# OSSI-1_OBC_2.net
KiCad netlist of a schematic drawn in Altium Designer
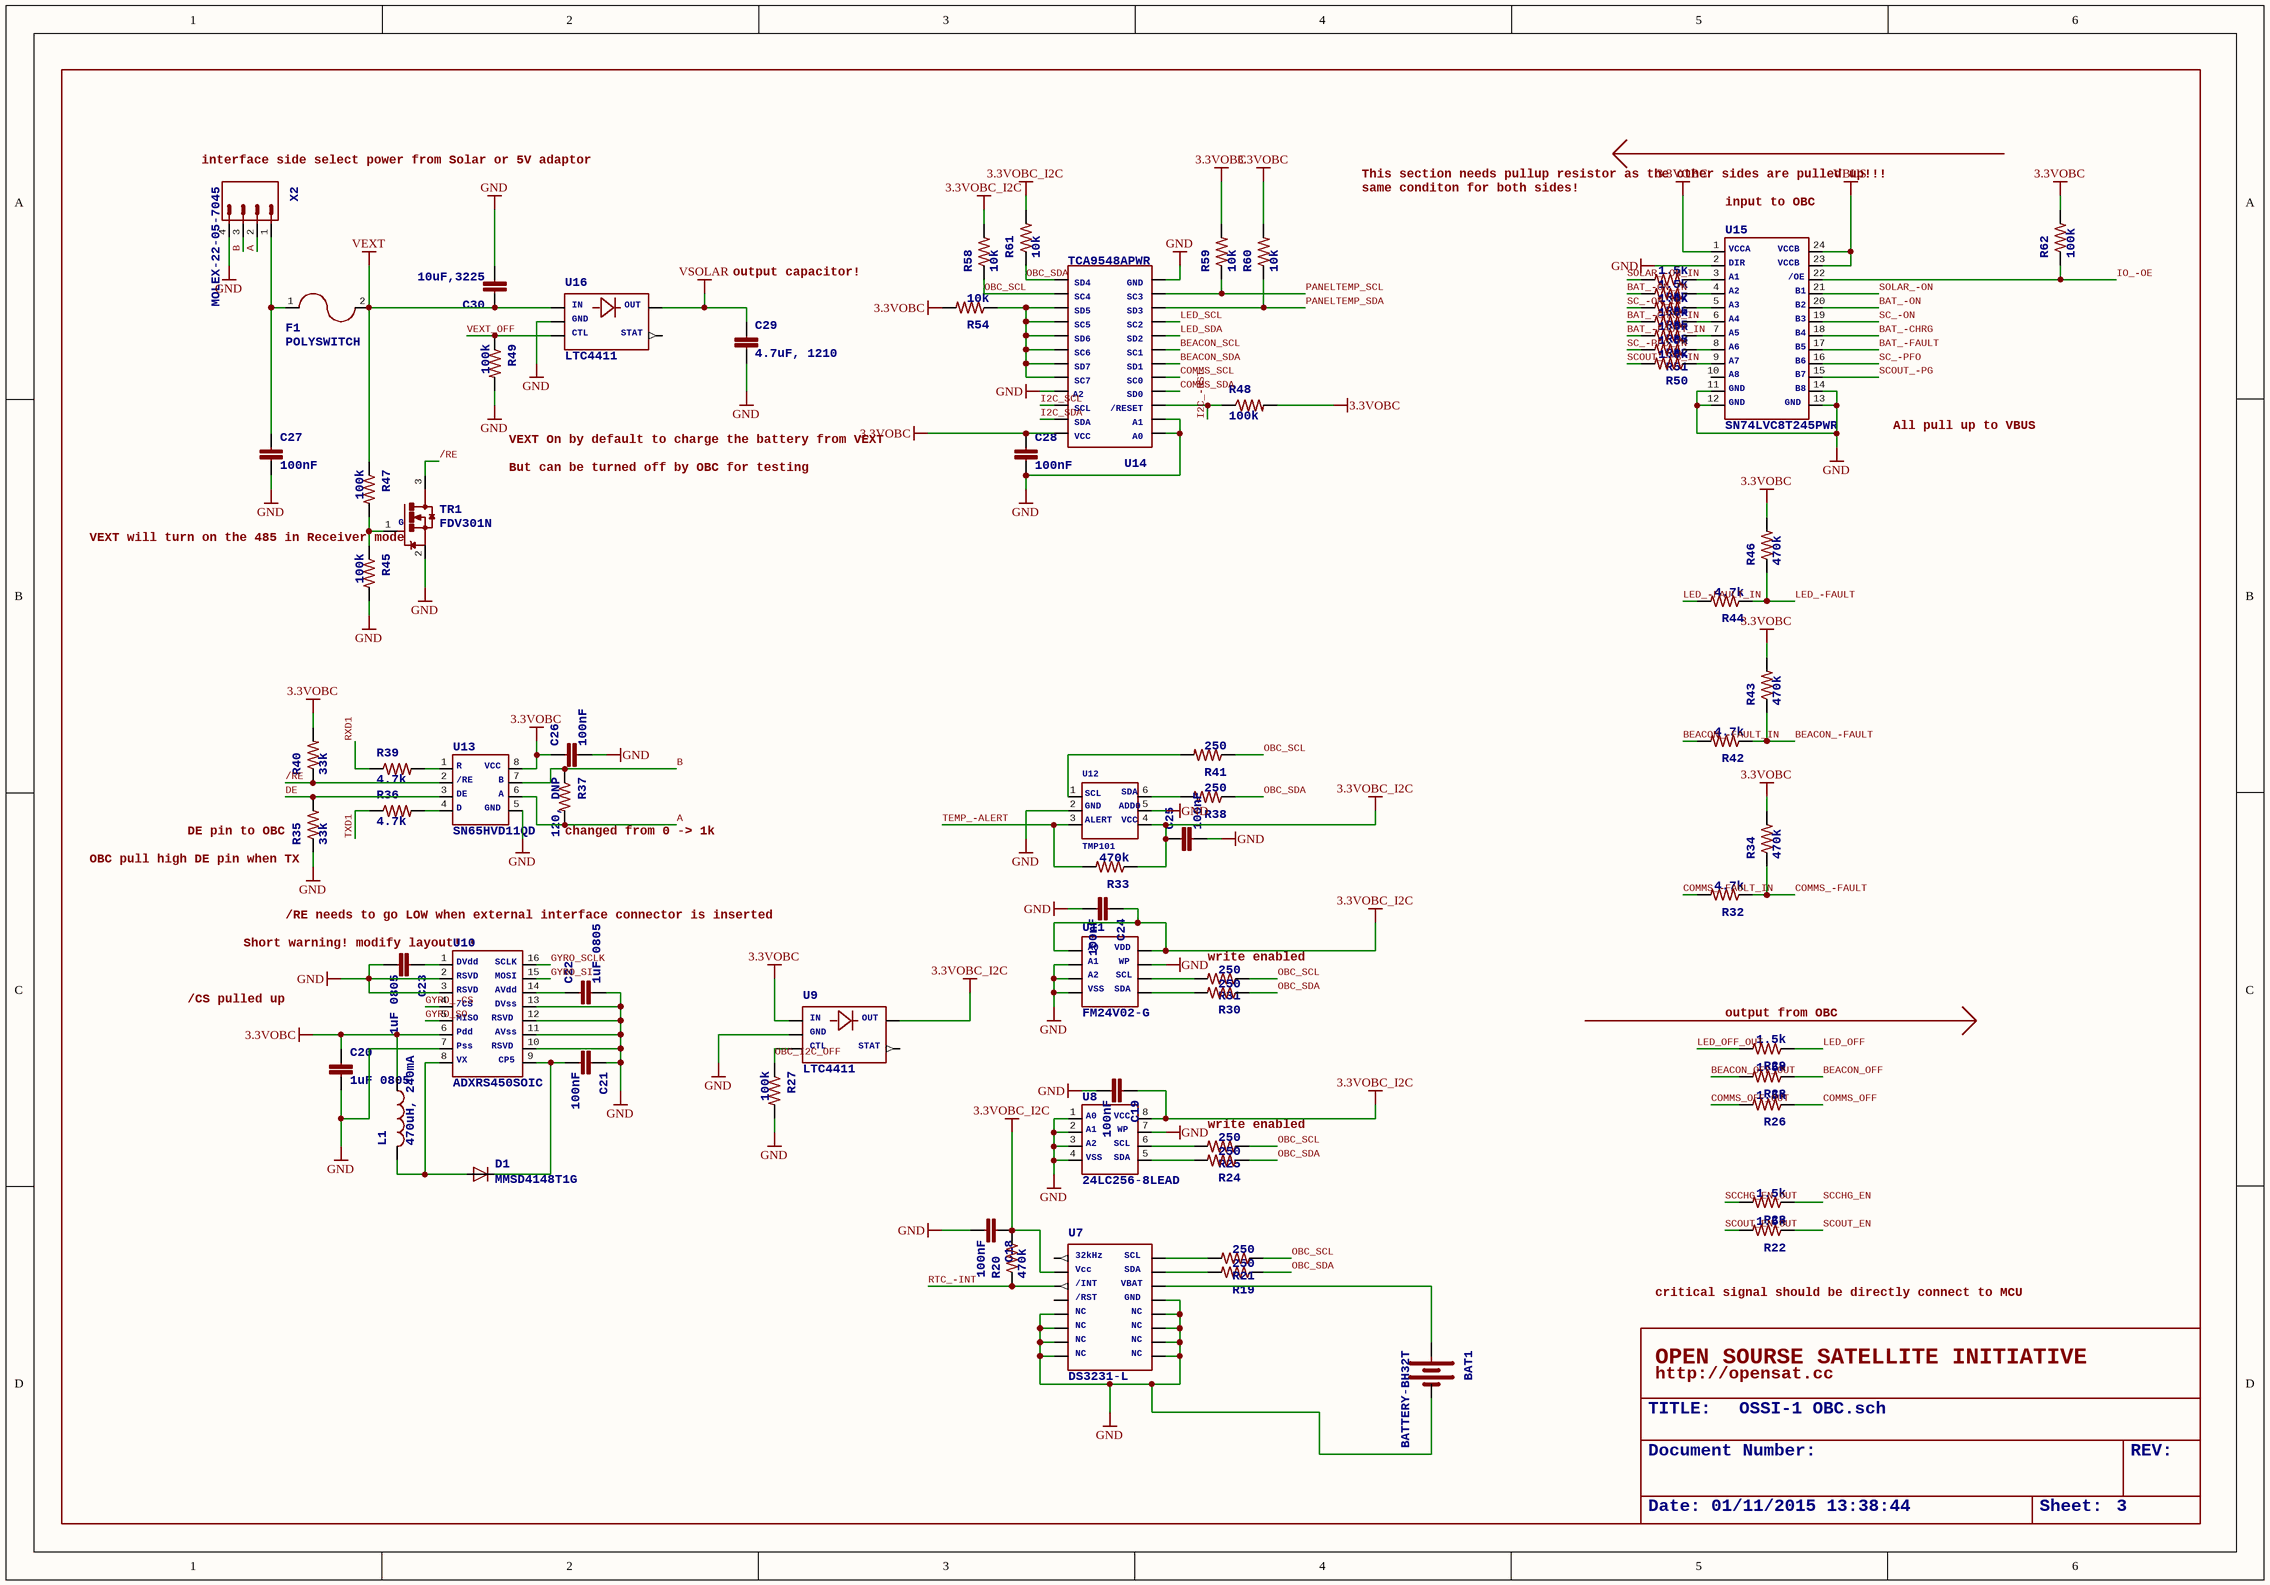
[diagram p0: OSSI-1 OBC_2.SchDoc]

(export (version "E")
  (design (tool "Eeschema 10.0.6"))
  (components
    (comp (ref "BAT1")
      (value "BATTERY-BH32T")
      (footprint "BH32T-C-G")
      (fields (field (name ">NAME") "BAT1") (field (name ">VALUE") "BATTERY-BH32T"))
      (libsource (lib "OSSI") (part "BATTERY-BH32T"))
    )
    (comp (ref "C18")
      (value "100nF")
      (footprint "C0603(1608)")
      (fields (field (name ">NAME") "C18") (field (name ">VALUE") "100nF"))
      (libsource (lib "OSSI") (part "C0603(1608)"))
    )
    (comp (ref "C19")
      (value "100nF")
      (footprint "C0603(1608)")
      (fields (field (name ">NAME") "C19") (field (name ">VALUE") "100nF"))
      (libsource (lib "OSSI") (part "C0603(1608)"))
    )
    (comp (ref "C20")
      (value "1uF 0805")
      (footprint "C0805(2012)")
      (fields (field (name ">NAME") "C20") (field (name ">VALUE") "1uF 0805"))
      (libsource (lib "") (part "C0805(2012)_2"))
    )
    (comp (ref "C21")
      (value "100nF")
      (footprint "C0603(1608)")
      (fields (field (name ">NAME") "C21") (field (name ">VALUE") "100nF"))
      (libsource (lib "OSSI") (part "C0603(1608)"))
    )
    (comp (ref "C22")
      (value "1uF 0805")
      (footprint "C0805(2012)")
      (fields (field (name ">NAME") "C22") (field (name ">VALUE") "1uF 0805"))
      (libsource (lib "OSSI") (part "C0805(2012)"))
    )
    (comp (ref "C23")
      (value "1uF 0805")
      (footprint "C0805(2012)")
      (fields (field (name ">NAME") "C23") (field (name ">VALUE") "1uF 0805"))
      (libsource (lib "") (part "C0805(2012)_1"))
    )
    (comp (ref "C24")
      (value "100nF")
      (footprint "C0603(1608)")
      (fields (field (name ">NAME") "C24") (field (name ">VALUE") "100nF"))
      (libsource (lib "OSSI") (part "C0603(1608)"))
    )
    (comp (ref "C25")
      (value "100nF")
      (footprint "C0603(1608)")
      (fields (field (name ">NAME") "C25") (field (name ">VALUE") "100nF"))
      (libsource (lib "") (part "C0603(1608)_1"))
    )
    (comp (ref "C26")
      (value "100nF")
      (footprint "C0603(1608)")
      (fields (field (name ">NAME") "C26") (field (name ">VALUE") "100nF"))
      (libsource (lib "") (part "C0603(1608)_1"))
    )
    (comp (ref "C27")
      (value "100nF")
      (footprint "C0603(1608)")
      (fields (field (name ">NAME") "C27") (field (name ">VALUE") "100nF"))
      (libsource (lib "") (part "C0603(1608)_2"))
    )
    (comp (ref "C28")
      (value "100nF")
      (footprint "C0603(1608)")
      (fields (field (name ">NAME") "C28") (field (name ">VALUE") "100nF"))
      (libsource (lib "") (part "C0603(1608)_2"))
    )
    (comp (ref "C29")
      (value "4.7uF, 1210")
      (footprint "C1206-GCM31")
      (fields (field (name ">NAME") "C29") (field (name ">VALUE") "4.7uF, 1210"))
      (libsource (lib "OSSI") (part "C1206(3216)-GCM31"))
    )
    (comp (ref "C30")
      (value "10uF,3225")
      (footprint "C1210-GCM32")
      (fields (field (name ">NAME") "C30") (field (name ">VALUE") "10uF,3225"))
      (libsource (lib "OSSI") (part "C1210(3225)-GCM32"))
    )
    (comp (ref "D1")
      (value "MMSD4148T1G")
      (footprint "SOD-123")
      (fields (field (name ">NAME") "D1") (field (name ">VALUE") "MMSD4148T1G"))
      (libsource (lib "OSSI") (part "MMSD4148T1G"))
    )
    (comp (ref "F1")
      (value "POLYSWITCH")
      (footprint "NANOSMDC150FCT")
      (description "Resettable Polyswitch")
      (fields (field (name ">NAME") "F1") (field (name ">VALUE") "POLYSWITCH"))
      (libsource (lib "OSSI") (part "POLYSWITCH"))
    )
    (comp (ref "L1")
      (value "470uH, 240mA")
      (footprint "L(2220)")
      (fields (field (name ">NAME") "L1") (field (name ">VALUE") "470uH, 240mA"))
      (libsource (lib "OSSI") (part "LQH55"))
    )
    (comp (ref "R19")
      (value "250")
      (footprint "R0603(1608)")
      (fields (field (name ">NAME") "R19") (field (name ">VALUE") "250"))
      (libsource (lib "OSSI") (part "R0603(1608)"))
    )
    (comp (ref "R20")
      (value "470k")
      (footprint "R0603(1608)")
      (fields (field (name ">NAME") "R20") (field (name ">VALUE") "470k"))
      (libsource (lib "OSSI") (part "R0603(1608)"))
    )
    (comp (ref "R21")
      (value "250")
      (footprint "R0603(1608)")
      (fields (field (name ">NAME") "R21") (field (name ">VALUE") "250"))
      (libsource (lib "OSSI") (part "R0603(1608)"))
    )
    (comp (ref "R22")
      (value "1.5k")
      (footprint "R0603(1608)")
      (fields (field (name ">NAME") "R22") (field (name ">VALUE") "1.5k"))
      (libsource (lib "OSSI") (part "R0603(1608)"))
    )
    (comp (ref "R23")
      (value "1.5k")
      (footprint "R0603(1608)")
      (fields (field (name ">NAME") "R23") (field (name ">VALUE") "1.5k"))
      (libsource (lib "OSSI") (part "R0603(1608)"))
    )
    (comp (ref "R24")
      (value "250")
      (footprint "R0603(1608)")
      (fields (field (name ">NAME") "R24") (field (name ">VALUE") "250"))
      (libsource (lib "OSSI") (part "R0603(1608)"))
    )
    (comp (ref "R25")
      (value "250")
      (footprint "R0603(1608)")
      (fields (field (name ">NAME") "R25") (field (name ">VALUE") "250"))
      (libsource (lib "OSSI") (part "R0603(1608)"))
    )
    (comp (ref "R26")
      (value "1.5k")
      (footprint "R0603(1608)")
      (fields (field (name ">NAME") "R26") (field (name ">VALUE") "1.5k"))
      (libsource (lib "OSSI") (part "R0603(1608)"))
    )
    (comp (ref "R27")
      (value "100k")
      (footprint "R0603(1608)")
      (fields (field (name ">NAME") "R27") (field (name ">VALUE") "100k"))
      (libsource (lib "OSSI") (part "R0603(1608)"))
    )
    (comp (ref "R28")
      (value "1.5k")
      (footprint "R0603(1608)")
      (fields (field (name ">NAME") "R28") (field (name ">VALUE") "1.5k"))
      (libsource (lib "OSSI") (part "R0603(1608)"))
    )
    (comp (ref "R29")
      (value "1.5k")
      (footprint "R0603(1608)")
      (fields (field (name ">NAME") "R29") (field (name ">VALUE") "1.5k"))
      (libsource (lib "OSSI") (part "R0603(1608)"))
    )
    (comp (ref "R30")
      (value "250")
      (footprint "R0603(1608)")
      (fields (field (name ">NAME") "R30") (field (name ">VALUE") "250"))
      (libsource (lib "OSSI") (part "R0603(1608)"))
    )
    (comp (ref "R31")
      (value "250")
      (footprint "R0603(1608)")
      (fields (field (name ">NAME") "R31") (field (name ">VALUE") "250"))
      (libsource (lib "OSSI") (part "R0603(1608)"))
    )
    (comp (ref "R32")
      (value "4.7k")
      (footprint "R0603(1608)")
      (fields (field (name ">NAME") "R32") (field (name ">VALUE") "4.7k"))
      (libsource (lib "OSSI") (part "R0603(1608)"))
    )
    (comp (ref "R33")
      (value "470k")
      (footprint "R0603(1608)")
      (fields (field (name ">NAME") "R33") (field (name ">VALUE") "470k"))
      (libsource (lib "OSSI") (part "R0603(1608)"))
    )
    (comp (ref "R34")
      (value "470k")
      (footprint "R0603(1608)")
      (fields (field (name ">NAME") "R34") (field (name ">VALUE") "470k"))
      (libsource (lib "OSSI") (part "R0603(1608)"))
    )
    (comp (ref "R35")
      (value "33k")
      (footprint "R0603(1608)")
      (fields (field (name ">NAME") "R35") (field (name ">VALUE") "33k"))
      (libsource (lib "OSSI") (part "R0603(1608)"))
    )
    (comp (ref "R36")
      (value "4.7k")
      (footprint "R0603(1608)")
      (fields (field (name ">NAME") "R36") (field (name ">VALUE") "4.7k"))
      (libsource (lib "OSSI") (part "R0603(1608)"))
    )
    (comp (ref "R37")
      (value "120, DNP")
      (footprint "R0603(1608)")
      (fields (field (name ">NAME") "R37") (field (name ">VALUE") "120, DNP"))
      (libsource (lib "OSSI") (part "R0603(1608)"))
    )
    (comp (ref "R38")
      (value "250")
      (footprint "R0603(1608)")
      (fields (field (name ">NAME") "R38") (field (name ">VALUE") "250"))
      (libsource (lib "OSSI") (part "R0603(1608)"))
    )
    (comp (ref "R39")
      (value "4.7k")
      (footprint "R0603(1608)")
      (fields (field (name ">NAME") "R39") (field (name ">VALUE") "4.7k"))
      (libsource (lib "OSSI") (part "R0603(1608)"))
    )
    (comp (ref "R40")
      (value "33k")
      (footprint "R0603(1608)")
      (fields (field (name ">NAME") "R40") (field (name ">VALUE") "33k"))
      (libsource (lib "OSSI") (part "R0603(1608)"))
    )
    (comp (ref "R41")
      (value "250")
      (footprint "R0603(1608)")
      (fields (field (name ">NAME") "R41") (field (name ">VALUE") "250"))
      (libsource (lib "OSSI") (part "R0603(1608)"))
    )
    (comp (ref "R42")
      (value "4.7k")
      (footprint "R0603(1608)")
      (fields (field (name ">NAME") "R42") (field (name ">VALUE") "4.7k"))
      (libsource (lib "OSSI") (part "R0603(1608)"))
    )
    (comp (ref "R43")
      (value "470k")
      (footprint "R0603(1608)")
      (fields (field (name ">NAME") "R43") (field (name ">VALUE") "470k"))
      (libsource (lib "OSSI") (part "R0603(1608)"))
    )
    (comp (ref "R44")
      (value "4.7k")
      (footprint "R0603(1608)")
      (fields (field (name ">NAME") "R44") (field (name ">VALUE") "4.7k"))
      (libsource (lib "OSSI") (part "R0603(1608)"))
    )
    (comp (ref "R45")
      (value "100k")
      (footprint "R0603(1608)")
      (fields (field (name ">NAME") "R45") (field (name ">VALUE") "100k"))
      (libsource (lib "OSSI") (part "R0603(1608)"))
    )
    (comp (ref "R46")
      (value "470k")
      (footprint "R0603(1608)")
      (fields (field (name ">NAME") "R46") (field (name ">VALUE") "470k"))
      (libsource (lib "OSSI") (part "R0603(1608)"))
    )
    (comp (ref "R47")
      (value "100k")
      (footprint "R0603(1608)")
      (fields (field (name ">NAME") "R47") (field (name ">VALUE") "100k"))
      (libsource (lib "OSSI") (part "R0603(1608)"))
    )
    (comp (ref "R48")
      (value "100k")
      (footprint "R0603(1608)")
      (fields (field (name ">NAME") "R48") (field (name ">VALUE") "100k"))
      (libsource (lib "OSSI") (part "R0603(1608)"))
    )
    (comp (ref "R49")
      (value "100k")
      (footprint "R0603(1608)")
      (fields (field (name ">NAME") "R49") (field (name ">VALUE") "100k"))
      (libsource (lib "OSSI") (part "R0603(1608)"))
    )
    (comp (ref "R50")
      (value "1.5k")
      (footprint "R0603(1608)")
      (fields (field (name ">NAME") "R50") (field (name ">VALUE") "1.5k"))
      (libsource (lib "OSSI") (part "R0603(1608)"))
    )
    (comp (ref "R51")
      (value "1.5k")
      (footprint "R0603(1608)")
      (fields (field (name ">NAME") "R51") (field (name ">VALUE") "1.5k"))
      (libsource (lib "OSSI") (part "R0603(1608)"))
    )
    (comp (ref "R52")
      (value "1.5k")
      (footprint "R0603(1608)")
      (fields (field (name ">NAME") "R52") (field (name ">VALUE") "1.5k"))
      (libsource (lib "OSSI") (part "R0603(1608)"))
    )
    (comp (ref "R53")
      (value "1.5k")
      (footprint "R0603(1608)")
      (fields (field (name ">NAME") "R53") (field (name ">VALUE") "1.5k"))
      (libsource (lib "OSSI") (part "R0603(1608)"))
    )
    (comp (ref "R54")
      (value "10k")
      (footprint "R0603(1608)")
      (fields (field (name ">NAME") "R54") (field (name ">VALUE") "10k"))
      (libsource (lib "OSSI") (part "R0603(1608)"))
    )
    (comp (ref "R55")
      (value "1.5k")
      (footprint "R0603(1608)")
      (fields (field (name ">NAME") "R55") (field (name ">VALUE") "1.5k"))
      (libsource (lib "OSSI") (part "R0603(1608)"))
    )
    (comp (ref "R56")
      (value "1.5k")
      (footprint "R0603(1608)")
      (fields (field (name ">NAME") "R56") (field (name ">VALUE") "1.5k"))
      (libsource (lib "OSSI") (part "R0603(1608)"))
    )
    (comp (ref "R57")
      (value "1.5k")
      (footprint "R0603(1608)")
      (fields (field (name ">NAME") "R57") (field (name ">VALUE") "1.5k"))
      (libsource (lib "OSSI") (part "R0603(1608)"))
    )
    (comp (ref "R58")
      (value "10k")
      (footprint "R0603(1608)")
      (fields (field (name ">NAME") "R58") (field (name ">VALUE") "10k"))
      (libsource (lib "OSSI") (part "R0603(1608)"))
    )
    (comp (ref "R59")
      (value "10k")
      (footprint "R0603(1608)")
      (fields (field (name ">NAME") "R59") (field (name ">VALUE") "10k"))
      (libsource (lib "OSSI") (part "R0603(1608)"))
    )
    (comp (ref "R60")
      (value "10k")
      (footprint "R0603(1608)")
      (fields (field (name ">NAME") "R60") (field (name ">VALUE") "10k"))
      (libsource (lib "OSSI") (part "R0603(1608)"))
    )
    (comp (ref "R61")
      (value "10k")
      (footprint "R0603(1608)")
      (fields (field (name ">NAME") "R61") (field (name ">VALUE") "10k"))
      (libsource (lib "OSSI") (part "R0603(1608)"))
    )
    (comp (ref "R62")
      (value "100k")
      (footprint "R0603(1608)")
      (fields (field (name ">NAME") "R62") (field (name ">VALUE") "100k"))
      (libsource (lib "OSSI") (part "R0603(1608)"))
    )
    (comp (ref "TR1")
      (value "FDV301N")
      (footprint "SOT23")
      (description "FDV301N Digital N channel - FET / Rdson = 5 Ohm / Vgs = 0.7~1.06V / Ids = 220mA")
      (fields (field (name "G") "G") (field (name ">NAME") "TR1") (field (name ">VALUE") "FDV301N"))
      (libsource (lib "OSSI") (part "FDV301N"))
    )
    (comp (ref "U7")
      (value "DS3231-L")
      (footprint "SO16L")
      (description "<b>DS3231</b>\n<br />\nExtremely Accureate I2C integrated RTC/TCXO/Crystal by MAXIM")
      (fields
        (field (name "32KHZ") "32kHz")
        (field (name "VCC") "Vcc")
        (field (name "/INT") "/INT")
        (field (name "/RST") "/RST")
        (field (name "NC") "NC")
        (field (name "NC_1") "NC")
        (field (name "NC_2") "NC")
        (field (name "NC_3") "NC")
        (field (name "NC_4") "NC")
        (field (name "NC_5") "NC")
        (field (name "NC_6") "NC")
        (field (name "NC_7") "NC")
        (field (name "GND") "GND")
        (field (name "VBAT") "VBAT")
        (field (name "SDA") "SDA")
        (field (name "SCL") "SCL")
        (field (name ">NAME") "U7")
        (field (name ">VALUE") "DS3231-L")
      )
      (libsource (lib "OSSI") (part "DS3231-L"))
    )
    (comp (ref "U8")
      (value "24LC256-8LEAD")
      (footprint "SO08-208")
      (description "24LC256<BR/>\n256K I2C™ CMOS Serial EEPROM")
      (fields
        (field (name ">NAME") "U8")
        (field (name ">VALUE") "24LC256-8LEAD")
        (field (name "A0") "A0")
        (field (name "A1") "A1")
        (field (name "A2") "A2")
        (field (name "VSS") "VSS")
        (field (name "VCC") "VCC")
        (field (name "WP") "WP")
        (field (name "SCL") "SCL")
        (field (name "SDA") "SDA")
      )
      (libsource (lib "OSSI") (part "24LC256-8LEAD"))
    )
    (comp (ref "U9")
      (value "LTC4411")
      (footprint "TSOT23-5")
      (fields
        (field (name "IN") "IN")
        (field (name "GND") "GND")
        (field (name "CTL") "CTL")
        (field (name "OUT") "OUT")
        (field (name "STAT") "STAT")
        (field (name ">NAME") "U9")
        (field (name ">VALUE") "LTC4411")
      )
      (libsource (lib "OSSI") (part "LTC4411"))
    )
    (comp (ref "U10")
      (value "ADXRS450SOIC")
      (footprint "SOIC-16CAV")
      (fields
        (field (name ">NAME") "U10")
        (field (name ">VALUE") "ADXRS450SOIC")
        (field (name "DVDD") "DVdd")
        (field (name "RSVD") "RSVD")
        (field (name "RSVD_1") "RSVD")
        (field (name "/CS") "/CS")
        (field (name "MISO") "MISO")
        (field (name "PDD") "Pdd")
        (field (name "PSS") "Pss")
        (field (name "VX") "VX")
        (field (name "CP5") "CP5")
        (field (name "RSVD_2") "RSVD")
        (field (name "AVSS") "AVss")
        (field (name "RSVD_3") "RSVD")
        (field (name "DVSS") "DVss")
        (field (name "AVDD") "AVdd")
        (field (name "MOSI") "MOSI")
        (field (name "SCLK") "SCLK")
      )
      (libsource (lib "OSSI") (part "ADXRS450SOIC"))
    )
    (comp (ref "U11")
      (value "FM24V02-G")
      (footprint "SO8")
      (description "<b>FM24V02</b>\n<br />\n256Kb Serial 3V F-RAM Memory by RAMTRON")
      (fields
        (field (name "A0") "A0")
        (field (name "A1") "A1")
        (field (name "A2") "A2")
        (field (name "VSS") "VSS")
        (field (name "SDA") "SDA")
        (field (name "SCL") "SCL")
        (field (name "WP") "WP")
        (field (name "VDD") "VDD")
        (field (name ">NAME") "U11")
        (field (name ">VALUE") "FM24V02-G")
      )
      (libsource (lib "OSSI") (part "FM24V02-G"))
    )
    (comp (ref "U12")
      (value "TMP101")
      (footprint "SOT23-6DBV")
      (description "TMP101 Digital Temerature Sensor with I2C Interface from Texas Instruments with Alert Function")
      (fields
        (field (name ">NAME") "U12")
        (field (name ">VALUE") "TMP101")
        (field (name "VCC") "VCC")
        (field (name "SCL") "SCL")
        (field (name "SDA") "SDA")
        (field (name "GND") "GND")
        (field (name "ADD0") "ADD0")
        (field (name "ALERT") "ALERT")
      )
      (libsource (lib "OSSI") (part "TMP101"))
    )
    (comp (ref "U13")
      (value "SN65HVD11QD")
      (footprint "SO8")
      (description "SN65HVD11 3.3V RS485 Transceiver <br />\nQD: -40~+125")
      (fields
        (field (name ">NAME") "U13")
        (field (name ">VALUE") "SN65HVD11QD")
        (field (name "R") "R")
        (field (name "/RE") "/RE")
        (field (name "DE") "DE")
        (field (name "D") "D")
        (field (name "VCC") "VCC")
        (field (name "B") "B")
        (field (name "A") "A")
        (field (name "GND") "GND")
      )
      (libsource (lib "OSSI") (part "SN65HVD11QD"))
    )
    (comp (ref "U14")
      (value "TCA9548APWR")
      (footprint "TSSOP-24-PW")
      (fields
        (field (name ">NAME") "U14")
        (field (name ">VALUE") "TCA9548APWR")
        (field (name "A0") "A0")
        (field (name "A1") "A1")
        (field (name "/RESET") "/RESET")
        (field (name "SD0") "SD0")
        (field (name "SC0") "SC0")
        (field (name "SD1") "SD1")
        (field (name "SC1") "SC1")
        (field (name "SD2") "SD2")
        (field (name "SC2") "SC2")
        (field (name "SD3") "SD3")
        (field (name "SC3") "SC3")
        (field (name "GND") "GND")
        (field (name "SD4") "SD4")
        (field (name "SC4") "SC4")
        (field (name "SD5") "SD5")
        (field (name "SC5") "SC5")
        (field (name "SD6") "SD6")
        (field (name "SC6") "SC6")
        (field (name "SD7") "SD7")
        (field (name "SC7") "SC7")
        (field (name "A2") "A2")
        (field (name "SCL") "SCL")
        (field (name "SDA") "SDA")
        (field (name "VCC") "VCC")
      )
      (libsource (lib "OSSI") (part "PCA9548APWR"))
    )
    (comp (ref "U15")
      (value "SN74LVC8T245PWR")
      (footprint "PW_R-PDSO-G24")
      (fields
        (field (name ">NAME") "U15")
        (field (name ">VALUE") "SN74LVC8T245PWR")
        (field (name "VCCA") "VCCA")
        (field (name "DIR") "DIR")
        (field (name "A1") "A1")
        (field (name "A2") "A2")
        (field (name "A3") "A3")
        (field (name "A4") "A4")
        (field (name "A5") "A5")
        (field (name "A6") "A6")
        (field (name "A7") "A7")
        (field (name "A8") "A8")
        (field (name "GND") "GND")
        (field (name "GND_1") "GND")
        (field (name "GND_2") "GND")
        (field (name "B1") "B1")
        (field (name "VCCB") "VCCB")
        (field (name "VCCB_1") "VCCB")
        (field (name "/OE") "/OE")
        (field (name "B2") "B2")
        (field (name "B3") "B3")
        (field (name "B4") "B4")
        (field (name "B5") "B5")
        (field (name "B6") "B6")
        (field (name "B7") "B7")
        (field (name "B8") "B8")
      )
      (libsource (lib "OSSI") (part "SN74LVC8T245PWR"))
    )
    (comp (ref "U16")
      (value "LTC4411")
      (footprint "TSOT23-5")
      (fields
        (field (name "IN") "IN")
        (field (name "GND") "GND")
        (field (name "CTL") "CTL")
        (field (name "OUT") "OUT")
        (field (name "STAT") "STAT")
        (field (name ">NAME") "U16")
        (field (name ">VALUE") "LTC4411")
      )
      (libsource (lib "OSSI") (part "LTC4411"))
    )
    (comp (ref "X2")
      (value "MOLEX-22-05-7045")
      (footprint "22-05-7045")
      (description "molex spoxt 5268 series 22-05-7045 for external interface")
      (fields (field (name ">NAME") "X2") (field (name ">VALUE") "MOLEX-22-05-7045"))
      (libsource (lib "OSSI") (part "MOLEX-22-05-7045"))
    )
  )
  (nets
    (net (code "1") (name "/A") (class "Default")
      (node (ref "R37") (pin "2") (pinfunction "2_2") (pintype "passive"))
      (node (ref "U13") (pin "6") (pinfunction "P$6_6") (pintype "passive"))
      (node (ref "X2") (pin "2") (pinfunction "2_2") (pintype "passive"))
    )
    (net (code "2") (name "/B") (class "Default")
      (node (ref "R37") (pin "1") (pinfunction "1_1") (pintype "passive"))
      (node (ref "U13") (pin "7") (pinfunction "P$7_7") (pintype "passive"))
      (node (ref "X2") (pin "3") (pinfunction "3_3") (pintype "passive"))
    )
    (net (code "3") (name "/BAT_-CHRG") (class "Default")
      (node (ref "U15") (pin "18") (pinfunction "P$18_18") (pintype "passive"))
    )
    (net (code "4") (name "/BAT_-CHRG_IN") (class "Default")
      (node (ref "R53") (pin "2") (pinfunction "2_2") (pintype "passive"))
    )
    (net (code "5") (name "/BAT_-FAULT") (class "Default")
      (node (ref "U15") (pin "17") (pinfunction "P$17_17") (pintype "passive"))
    )
    (net (code "6") (name "/BAT_-FAULT_IN") (class "Default")
      (node (ref "R52") (pin "2") (pinfunction "2_2") (pintype "passive"))
    )
    (net (code "7") (name "/BAT_-ON") (class "Default")
      (node (ref "U15") (pin "20") (pinfunction "P$20_20") (pintype "passive"))
    )
    (net (code "8") (name "/BAT_-ON_IN") (class "Default")
      (node (ref "R56") (pin "2") (pinfunction "2_2") (pintype "passive"))
    )
    (net (code "9") (name "/BEACON_-FAULT") (class "Default")
      (node (ref "R42") (pin "1") (pinfunction "1_1") (pintype "passive"))
      (node (ref "R43") (pin "1") (pinfunction "1_1") (pintype "passive"))
    )
    (net (code "10") (name "/BEACON_-FAULT_IN") (class "Default")
      (node (ref "R42") (pin "2") (pinfunction "2_2") (pintype "passive"))
    )
    (net (code "11") (name "/BEACON_OFF") (class "Default")
      (node (ref "R28") (pin "1") (pinfunction "1_1") (pintype "passive"))
    )
    (net (code "12") (name "/BEACON_OFF_OUT") (class "Default")
      (node (ref "R28") (pin "2") (pinfunction "2_2") (pintype "passive"))
    )
    (net (code "13") (name "/BEACON_SCL") (class "Default")
      (node (ref "U14") (pin "7") (pinfunction "P$7_7") (pintype "passive"))
    )
    (net (code "14") (name "/BEACON_SDA") (class "Default")
      (node (ref "U14") (pin "6") (pinfunction "P$6_6") (pintype "passive"))
    )
    (net (code "15") (name "/COMMS_-FAULT") (class "Default")
      (node (ref "R32") (pin "1") (pinfunction "1_1") (pintype "passive"))
      (node (ref "R34") (pin "1") (pinfunction "1_1") (pintype "passive"))
    )
    (net (code "16") (name "/COMMS_-FAULT_IN") (class "Default")
      (node (ref "R32") (pin "2") (pinfunction "2_2") (pintype "passive"))
    )
    (net (code "17") (name "/COMMS_OFF") (class "Default")
      (node (ref "R26") (pin "1") (pinfunction "1_1") (pintype "passive"))
    )
    (net (code "18") (name "/COMMS_OFF_OUT") (class "Default")
      (node (ref "R26") (pin "2") (pinfunction "2_2") (pintype "passive"))
    )
    (net (code "19") (name "/COMMS_SCL") (class "Default")
      (node (ref "U14") (pin "5") (pinfunction "P$5_5") (pintype "passive"))
    )
    (net (code "20") (name "/COMMS_SDA") (class "Default")
      (node (ref "U14") (pin "4") (pinfunction "P$4_4") (pintype "passive"))
    )
    (net (code "21") (name "/DE") (class "Default")
      (node (ref "R35") (pin "2") (pinfunction "2_2") (pintype "passive"))
      (node (ref "U13") (pin "3") (pinfunction "P$3_3") (pintype "passive"))
    )
    (net (code "22") (name "/GYRO_-CS") (class "Default")
      (node (ref "U10") (pin "4") (pinfunction "P$4_4") (pintype "passive"))
    )
    (net (code "23") (name "/GYRO_SCLK") (class "Default")
      (node (ref "U10") (pin "16") (pinfunction "P$16_16") (pintype "passive"))
    )
    (net (code "24") (name "/GYRO_SI") (class "Default")
      (node (ref "U10") (pin "15") (pinfunction "P$15_15") (pintype "passive"))
    )
    (net (code "25") (name "/GYRO_SO") (class "Default")
      (node (ref "U10") (pin "5") (pinfunction "P$5_5") (pintype "passive"))
    )
    (net (code "26") (name "/I2C_-RST") (class "Default")
      (node (ref "R48") (pin "1") (pinfunction "1_1") (pintype "passive"))
      (node (ref "U14") (pin "3") (pinfunction "P$3_3") (pintype "passive"))
    )
    (net (code "27") (name "/I2C_SCL") (class "Default")
      (node (ref "U14") (pin "22") (pinfunction "P$22_22") (pintype "passive"))
    )
    (net (code "28") (name "/I2C_SDA") (class "Default")
      (node (ref "U14") (pin "23") (pinfunction "P$23_23") (pintype "passive"))
    )
    (net (code "29") (name "/IO_-OE") (class "Default")
      (node (ref "R62") (pin "1") (pinfunction "1_1") (pintype "passive"))
      (node (ref "U15") (pin "22") (pinfunction "P$22_22") (pintype "passive"))
    )
    (net (code "30") (name "/LED_-FAULT") (class "Default")
      (node (ref "R44") (pin "1") (pinfunction "1_1") (pintype "passive"))
      (node (ref "R46") (pin "1") (pinfunction "1_1") (pintype "passive"))
    )
    (net (code "31") (name "/LED_-FAULT_IN") (class "Default")
      (node (ref "R44") (pin "2") (pinfunction "2_2") (pintype "passive"))
    )
    (net (code "32") (name "/LED_OFF") (class "Default")
      (node (ref "R29") (pin "1") (pinfunction "1_1") (pintype "passive"))
    )
    (net (code "33") (name "/LED_OFF_OUT") (class "Default")
      (node (ref "R29") (pin "2") (pinfunction "2_2") (pintype "passive"))
    )
    (net (code "34") (name "/LED_SCL") (class "Default")
      (node (ref "U14") (pin "9") (pinfunction "P$9_9") (pintype "passive"))
    )
    (net (code "35") (name "/LED_SDA") (class "Default")
      (node (ref "U14") (pin "8") (pinfunction "P$8_8") (pintype "passive"))
    )
    (net (code "36") (name "/OBC_I2C_OFF") (class "Default")
      (node (ref "R27") (pin "1") (pinfunction "1_1") (pintype "passive"))
      (node (ref "U9") (pin "P$3") (pinfunction "P$3_P$3") (pintype "passive"))
    )
    (net (code "37") (name "/OBC_SCL") (class "Default")
      (node (ref "R21") (pin "1") (pinfunction "1_1") (pintype "passive"))
      (node (ref "R25") (pin "1") (pinfunction "1_1") (pintype "passive"))
      (node (ref "R31") (pin "1") (pinfunction "1_1") (pintype "passive"))
      (node (ref "R41") (pin "1") (pinfunction "1_1") (pintype "passive"))
      (node (ref "R58") (pin "1") (pinfunction "1_1") (pintype "passive"))
      (node (ref "U14") (pin "14") (pinfunction "P$14_14") (pintype "passive"))
    )
    (net (code "38") (name "/OBC_SDA") (class "Default")
      (node (ref "R19") (pin "1") (pinfunction "1_1") (pintype "passive"))
      (node (ref "R24") (pin "1") (pinfunction "1_1") (pintype "passive"))
      (node (ref "R30") (pin "1") (pinfunction "1_1") (pintype "passive"))
      (node (ref "R38") (pin "1") (pinfunction "1_1") (pintype "passive"))
      (node (ref "R61") (pin "1") (pinfunction "1_1") (pintype "passive"))
      (node (ref "U14") (pin "13") (pinfunction "P$13_13") (pintype "passive"))
    )
    (net (code "39") (name "/PANELTEMP_SCL") (class "Default")
      (node (ref "R59") (pin "1") (pinfunction "1_1") (pintype "passive"))
      (node (ref "U14") (pin "11") (pinfunction "P$11_11") (pintype "passive"))
    )
    (net (code "40") (name "/PANELTEMP_SDA") (class "Default")
      (node (ref "R60") (pin "1") (pinfunction "1_1") (pintype "passive"))
      (node (ref "U14") (pin "10") (pinfunction "P$10_10") (pintype "passive"))
    )
    (net (code "41") (name "/RTC_-INT") (class "Default")
      (node (ref "R20") (pin "1") (pinfunction "1_1") (pintype "passive"))
      (node (ref "U7") (pin "3") (pinfunction "P$3_3") (pintype "output"))
    )
    (net (code "42") (name "/RXD1") (class "Default")
      (node (ref "R39") (pin "1") (pinfunction "1_1") (pintype "passive"))
    )
    (net (code "43") (name "/SCCHG_EN") (class "Default")
      (node (ref "R23") (pin "1") (pinfunction "1_1") (pintype "passive"))
    )
    (net (code "44") (name "/SCCHG_EN_OUT") (class "Default")
      (node (ref "R23") (pin "2") (pinfunction "2_2") (pintype "passive"))
    )
    (net (code "45") (name "/SCOUT_-PG") (class "Default")
      (node (ref "U15") (pin "15") (pinfunction "P$15_15") (pintype "passive"))
    )
    (net (code "46") (name "/SCOUT_-PG_IN") (class "Default")
      (node (ref "R50") (pin "2") (pinfunction "2_2") (pintype "passive"))
    )
    (net (code "47") (name "/SCOUT_EN") (class "Default")
      (node (ref "R22") (pin "1") (pinfunction "1_1") (pintype "passive"))
    )
    (net (code "48") (name "/SCOUT_EN_OUT") (class "Default")
      (node (ref "R22") (pin "2") (pinfunction "2_2") (pintype "passive"))
    )
    (net (code "49") (name "/SC_-ON") (class "Default")
      (node (ref "U15") (pin "19") (pinfunction "P$19_19") (pintype "passive"))
    )
    (net (code "50") (name "/SC_-ON_IN") (class "Default")
      (node (ref "R55") (pin "2") (pinfunction "2_2") (pintype "passive"))
    )
    (net (code "51") (name "/SC_-PFO") (class "Default")
      (node (ref "U15") (pin "16") (pinfunction "P$16_16") (pintype "passive"))
    )
    (net (code "52") (name "/SC_-PFO_IN") (class "Default")
      (node (ref "R51") (pin "2") (pinfunction "2_2") (pintype "passive"))
    )
    (net (code "53") (name "/SOLAR_-ON") (class "Default")
      (node (ref "U15") (pin "21") (pinfunction "P$21_21") (pintype "passive"))
    )
    (net (code "54") (name "/SOLAR_-ON_IN") (class "Default")
      (node (ref "R57") (pin "2") (pinfunction "2_2") (pintype "passive"))
    )
    (net (code "55") (name "/TEMP_-ALERT") (class "Default")
      (node (ref "R33") (pin "2") (pinfunction "2_2") (pintype "passive"))
      (node (ref "U12") (pin "3") (pinfunction "3_3") (pintype "passive"))
    )
    (net (code "56") (name "/TXD1") (class "Default")
      (node (ref "R36") (pin "1") (pinfunction "1_1") (pintype "passive"))
    )
    (net (code "57") (name "/VEXT_OFF") (class "Default")
      (node (ref "R49") (pin "1") (pinfunction "1_1") (pintype "passive"))
      (node (ref "U16") (pin "P$3") (pinfunction "P$3_P$3") (pintype "passive"))
    )
    (net (code "58") (name "/{slash}RE") (class "Default")
      (node (ref "R40") (pin "1") (pinfunction "1_1") (pintype "passive"))
      (node (ref "TR1") (pin "3") (pinfunction "D_3") (pintype "passive"))
      (node (ref "U13") (pin "2") (pinfunction "P$2_2") (pintype "passive"))
    )
    (net (code "59") (name "3.3VOBC") (class "Default")
      (node (ref "C20") (pin "1") (pinfunction "1_1") (pintype "passive"))
      (node (ref "C26") (pin "1") (pinfunction "1_1") (pintype "passive"))
      (node (ref "C28") (pin "1") (pinfunction "1_1") (pintype "passive"))
      (node (ref "L1") (pin "P$1") (pinfunction "1_P$1") (pintype "passive"))
      (node (ref "R34") (pin "2") (pinfunction "2_2") (pintype "passive"))
      (node (ref "R40") (pin "2") (pinfunction "2_2") (pintype "passive"))
      (node (ref "R43") (pin "2") (pinfunction "2_2") (pintype "passive"))
      (node (ref "R46") (pin "2") (pinfunction "2_2") (pintype "passive"))
      (node (ref "R48") (pin "2") (pinfunction "2_2") (pintype "passive"))
      (node (ref "R54") (pin "2") (pinfunction "2_2") (pintype "passive"))
      (node (ref "R59") (pin "2") (pinfunction "2_2") (pintype "passive"))
      (node (ref "R60") (pin "2") (pinfunction "2_2") (pintype "passive"))
      (node (ref "R62") (pin "2") (pinfunction "2_2") (pintype "passive"))
      (node (ref "U10") (pin "6") (pinfunction "P$6_6") (pintype "power_in"))
      (node (ref "U13") (pin "8") (pinfunction "P$8_8") (pintype "passive"))
      (node (ref "U14") (pin "24") (pinfunction "P$24_24") (pintype "power_in"))
      (node (ref "U15") (pin "1") (pinfunction "P$1_1") (pintype "passive"))
      (node (ref "U9") (pin "P$1") (pinfunction "P$1_P$1") (pintype "passive"))
    )
    (net (code "60") (name "3.3VOBC_I2C") (class "Default")
      (node (ref "C18") (pin "1") (pinfunction "1_1") (pintype "passive"))
      (node (ref "C19") (pin "1") (pinfunction "1_1") (pintype "passive"))
      (node (ref "C24") (pin "1") (pinfunction "1_1") (pintype "passive"))
      (node (ref "C25") (pin "1") (pinfunction "1_1") (pintype "passive"))
      (node (ref "R20") (pin "2") (pinfunction "2_2") (pintype "passive"))
      (node (ref "R33") (pin "1") (pinfunction "1_1") (pintype "passive"))
      (node (ref "R58") (pin "2") (pinfunction "2_2") (pintype "passive"))
      (node (ref "R61") (pin "2") (pinfunction "2_2") (pintype "passive"))
      (node (ref "U11") (pin "1") (pinfunction "A0_1") (pintype "passive"))
      (node (ref "U11") (pin "8") (pinfunction "VDD_8") (pintype "power_in"))
      (node (ref "U12") (pin "4") (pinfunction "4_4") (pintype "passive"))
      (node (ref "U7") (pin "2") (pinfunction "P$2_2") (pintype "power_in"))
      (node (ref "U8") (pin "8") (pinfunction "P$8_8") (pintype "passive"))
      (node (ref "U9") (pin "P$5") (pinfunction "P$5_P$5") (pintype "power_in"))
    )
    (net (code "61") (name "GND") (class "Default")
      (node (ref "BAT1") (pin "N") (pinfunction "-_N") (pintype "power_in"))
      (node (ref "C18") (pin "2") (pinfunction "2_2") (pintype "passive"))
      (node (ref "C19") (pin "2") (pinfunction "2_2") (pintype "passive"))
      (node (ref "C20") (pin "2") (pinfunction "2_2") (pintype "passive"))
      (node (ref "C21") (pin "1") (pinfunction "1_1") (pintype "passive"))
      (node (ref "C22") (pin "2") (pinfunction "2_2") (pintype "passive"))
      (node (ref "C23") (pin "2") (pinfunction "2_2") (pintype "passive"))
      (node (ref "C24") (pin "2") (pinfunction "2_2") (pintype "passive"))
      (node (ref "C25") (pin "2") (pinfunction "2_2") (pintype "passive"))
      (node (ref "C26") (pin "2") (pinfunction "2_2") (pintype "passive"))
      (node (ref "C27") (pin "2") (pinfunction "2_2") (pintype "passive"))
      (node (ref "C28") (pin "2") (pinfunction "2_2") (pintype "passive"))
      (node (ref "C29") (pin "P$2") (pinfunction "2_P$2") (pintype "passive"))
      (node (ref "C30") (pin "P$2") (pinfunction "2_P$2") (pintype "passive"))
      (node (ref "R27") (pin "2") (pinfunction "2_2") (pintype "passive"))
      (node (ref "R35") (pin "1") (pinfunction "1_1") (pintype "passive"))
      (node (ref "R45") (pin "2") (pinfunction "2_2") (pintype "passive"))
      (node (ref "R49") (pin "2") (pinfunction "2_2") (pintype "passive"))
      (node (ref "TR1") (pin "2") (pinfunction "S_2") (pintype "passive"))
      (node (ref "U10") (pin "10") (pinfunction "P$10_10") (pintype "power_in"))
      (node (ref "U10") (pin "11") (pinfunction "P$11_11") (pintype "power_in"))
      (node (ref "U10") (pin "12") (pinfunction "P$12_12") (pintype "power_in"))
      (node (ref "U10") (pin "13") (pinfunction "P$13_13") (pintype "power_in"))
      (node (ref "U10") (pin "2") (pinfunction "P$2_2") (pintype "power_in"))
      (node (ref "U10") (pin "3") (pinfunction "P$3_3") (pintype "power_in"))
      (node (ref "U10") (pin "7") (pinfunction "P$7_7") (pintype "power_in"))
      (node (ref "U11") (pin "2") (pinfunction "A1_2") (pintype "passive"))
      (node (ref "U11") (pin "3") (pinfunction "A2_3") (pintype "passive"))
      (node (ref "U11") (pin "4") (pinfunction "VSS_4") (pintype "power_in"))
      (node (ref "U11") (pin "7") (pinfunction "WP_7") (pintype "passive"))
      (node (ref "U12") (pin "2") (pinfunction "2_2") (pintype "passive"))
      (node (ref "U12") (pin "5") (pinfunction "5_5") (pintype "passive"))
      (node (ref "U13") (pin "5") (pinfunction "P$5_5") (pintype "passive"))
      (node (ref "U14") (pin "1") (pinfunction "P$1_1") (pintype "passive"))
      (node (ref "U14") (pin "12") (pinfunction "P$12_12") (pintype "power_in"))
      (node (ref "U14") (pin "2") (pinfunction "P$2_2") (pintype "passive"))
      (node (ref "U14") (pin "21") (pinfunction "P$21_21") (pintype "passive"))
      (node (ref "U15") (pin "11") (pinfunction "P$11_11") (pintype "passive"))
      (node (ref "U15") (pin "12") (pinfunction "P$12_12") (pintype "passive"))
      (node (ref "U15") (pin "13") (pinfunction "P$13_13") (pintype "passive"))
      (node (ref "U15") (pin "14") (pinfunction "P$14_14") (pintype "passive"))
      (node (ref "U15") (pin "2") (pinfunction "P$2_2") (pintype "passive"))
      (node (ref "U16") (pin "P$2") (pinfunction "P$2_P$2") (pintype "power_in"))
      (node (ref "U7") (pin "10") (pinfunction "P$10_10") (pintype "passive"))
      (node (ref "U7") (pin "11") (pinfunction "P$11_11") (pintype "passive"))
      (node (ref "U7") (pin "12") (pinfunction "P$12_12") (pintype "passive"))
      (node (ref "U7") (pin "13") (pinfunction "P$13_13") (pintype "power_in"))
      (node (ref "U7") (pin "5") (pinfunction "P$5_5") (pintype "passive"))
      (node (ref "U7") (pin "6") (pinfunction "P$6_6") (pintype "passive"))
      (node (ref "U7") (pin "7") (pinfunction "P$7_7") (pintype "passive"))
      (node (ref "U7") (pin "8") (pinfunction "P$8_8") (pintype "passive"))
      (node (ref "U7") (pin "9") (pinfunction "P$9_9") (pintype "passive"))
      (node (ref "U8") (pin "1") (pinfunction "P$1_1") (pintype "passive"))
      (node (ref "U8") (pin "2") (pinfunction "P$2_2") (pintype "passive"))
      (node (ref "U8") (pin "3") (pinfunction "P$3_3") (pintype "passive"))
      (node (ref "U8") (pin "4") (pinfunction "P$4_4") (pintype "passive"))
      (node (ref "U8") (pin "7") (pinfunction "P$7_7") (pintype "passive"))
      (node (ref "U9") (pin "P$2") (pinfunction "P$2_P$2") (pintype "power_in"))
      (node (ref "X2") (pin "4") (pinfunction "4_4") (pintype "passive"))
    )
    (net (code "62") (name "Net-(BAT1-+)") (class "Default")
      (node (ref "BAT1") (pin "P") (pinfunction "+_P") (pintype "power_in"))
      (node (ref "U7") (pin "14") (pinfunction "P$14_14") (pintype "power_in"))
    )
    (net (code "63") (name "Net-(F1-P$1)") (class "Default")
      (node (ref "C27") (pin "1") (pinfunction "1_1") (pintype "passive"))
      (node (ref "F1") (pin "1") (pinfunction "P$1_1") (pintype "passive"))
      (node (ref "X2") (pin "1") (pinfunction "1_1") (pintype "passive"))
    )
    (net (code "64") (name "Net-(L1-2)") (class "Default")
      (node (ref "D1") (pin "A") (pinfunction "A_A") (pintype "passive"))
      (node (ref "L1") (pin "P$2") (pinfunction "2_P$2") (pintype "passive"))
      (node (ref "U10") (pin "8") (pinfunction "P$8_8") (pintype "power_in"))
    )
    (net (code "65") (name "Net-(R38-Pad2)") (class "Default")
      (node (ref "R38") (pin "2") (pinfunction "2_2") (pintype "passive"))
      (node (ref "U12") (pin "6") (pinfunction "6_6") (pintype "passive"))
    )
    (net (code "66") (name "Net-(R41-Pad2)") (class "Default")
      (node (ref "R41") (pin "2") (pinfunction "2_2") (pintype "passive"))
      (node (ref "U12") (pin "1") (pinfunction "1_1") (pintype "passive"))
    )
    (net (code "67") (name "Net-(TR1-G)") (class "Default")
      (node (ref "R45") (pin "1") (pinfunction "1_1") (pintype "passive"))
      (node (ref "R47") (pin "2") (pinfunction "2_2") (pintype "passive"))
      (node (ref "TR1") (pin "1") (pinfunction "G_1") (pintype "passive"))
    )
    (net (code "68") (name "Net-(U7-P$15)") (class "Default")
      (node (ref "R19") (pin "2") (pinfunction "2_2") (pintype "passive"))
      (node (ref "U7") (pin "15") (pinfunction "P$15_15") (pintype "passive"))
    )
    (net (code "69") (name "Net-(U7-P$16)") (class "Default")
      (node (ref "R21") (pin "2") (pinfunction "2_2") (pintype "passive"))
      (node (ref "U7") (pin "16") (pinfunction "P$16_16") (pintype "passive"))
    )
    (net (code "70") (name "Net-(U8-P$5)") (class "Default")
      (node (ref "R24") (pin "2") (pinfunction "2_2") (pintype "passive"))
      (node (ref "U8") (pin "5") (pinfunction "P$5_5") (pintype "passive"))
    )
    (net (code "71") (name "Net-(U8-P$6)") (class "Default")
      (node (ref "R25") (pin "2") (pinfunction "2_2") (pintype "passive"))
      (node (ref "U8") (pin "6") (pinfunction "P$6_6") (pintype "passive"))
    )
    (net (code "72") (name "Net-(U10-P$1)") (class "Default")
      (node (ref "C23") (pin "1") (pinfunction "1_1") (pintype "passive"))
      (node (ref "U10") (pin "1") (pinfunction "P$1_1") (pintype "power_in"))
    )
    (net (code "73") (name "Net-(U10-P$9)") (class "Default")
      (node (ref "C21") (pin "2") (pinfunction "2_2") (pintype "passive"))
      (node (ref "D1") (pin "C") (pinfunction "C_C") (pintype "passive"))
      (node (ref "U10") (pin "9") (pinfunction "P$9_9") (pintype "power_in"))
    )
    (net (code "74") (name "Net-(U10-P$14)") (class "Default")
      (node (ref "C22") (pin "1") (pinfunction "1_1") (pintype "passive"))
      (node (ref "U10") (pin "14") (pinfunction "P$14_14") (pintype "power_in"))
    )
    (net (code "75") (name "Net-(U11-SCL)") (class "Default")
      (node (ref "R31") (pin "2") (pinfunction "2_2") (pintype "passive"))
      (node (ref "U11") (pin "6") (pinfunction "SCL_6") (pintype "passive"))
    )
    (net (code "76") (name "Net-(U11-SDA)") (class "Default")
      (node (ref "R30") (pin "2") (pinfunction "2_2") (pintype "passive"))
      (node (ref "U11") (pin "5") (pinfunction "SDA_5") (pintype "passive"))
    )
    (net (code "77") (name "Net-(U13-P$1)") (class "Default")
      (node (ref "R39") (pin "2") (pinfunction "2_2") (pintype "passive"))
      (node (ref "U13") (pin "1") (pinfunction "P$1_1") (pintype "passive"))
    )
    (net (code "78") (name "Net-(U13-P$4)") (class "Default")
      (node (ref "R36") (pin "2") (pinfunction "2_2") (pintype "passive"))
      (node (ref "U13") (pin "4") (pinfunction "P$4_4") (pintype "passive"))
    )
    (net (code "79") (name "Net-(U14-P$15)") (class "Default")
      (node (ref "R54") (pin "1") (pinfunction "1_1") (pintype "passive"))
      (node (ref "U14") (pin "15") (pinfunction "P$15_15") (pintype "passive"))
      (node (ref "U14") (pin "16") (pinfunction "P$16_16") (pintype "passive"))
      (node (ref "U14") (pin "17") (pinfunction "P$17_17") (pintype "passive"))
      (node (ref "U14") (pin "18") (pinfunction "P$18_18") (pintype "passive"))
      (node (ref "U14") (pin "19") (pinfunction "P$19_19") (pintype "passive"))
      (node (ref "U14") (pin "20") (pinfunction "P$20_20") (pintype "passive"))
    )
    (net (code "80") (name "Net-(U15-P$3)") (class "Default")
      (node (ref "R57") (pin "1") (pinfunction "1_1") (pintype "passive"))
      (node (ref "U15") (pin "3") (pinfunction "P$3_3") (pintype "passive"))
    )
    (net (code "81") (name "Net-(U15-P$4)") (class "Default")
      (node (ref "R56") (pin "1") (pinfunction "1_1") (pintype "passive"))
      (node (ref "U15") (pin "4") (pinfunction "P$4_4") (pintype "passive"))
    )
    (net (code "82") (name "Net-(U15-P$5)") (class "Default")
      (node (ref "R55") (pin "1") (pinfunction "1_1") (pintype "passive"))
      (node (ref "U15") (pin "5") (pinfunction "P$5_5") (pintype "passive"))
    )
    (net (code "83") (name "Net-(U15-P$6)") (class "Default")
      (node (ref "R53") (pin "1") (pinfunction "1_1") (pintype "passive"))
      (node (ref "U15") (pin "6") (pinfunction "P$6_6") (pintype "passive"))
    )
    (net (code "84") (name "Net-(U15-P$7)") (class "Default")
      (node (ref "R52") (pin "1") (pinfunction "1_1") (pintype "passive"))
      (node (ref "U15") (pin "7") (pinfunction "P$7_7") (pintype "passive"))
    )
    (net (code "85") (name "Net-(U15-P$8)") (class "Default")
      (node (ref "R51") (pin "1") (pinfunction "1_1") (pintype "passive"))
      (node (ref "U15") (pin "8") (pinfunction "P$8_8") (pintype "passive"))
    )
    (net (code "86") (name "Net-(U15-P$9)") (class "Default")
      (node (ref "R50") (pin "1") (pinfunction "1_1") (pintype "passive"))
      (node (ref "U15") (pin "9") (pinfunction "P$9_9") (pintype "passive"))
    )
    (net (code "87") (name "VBUS") (class "Default")
      (node (ref "U15") (pin "23") (pinfunction "P$23_23") (pintype "passive"))
      (node (ref "U15") (pin "24") (pinfunction "P$24_24") (pintype "passive"))
    )
    (net (code "88") (name "VEXT") (class "Default")
      (node (ref "C30") (pin "P$1") (pinfunction "1_P$1") (pintype "passive"))
      (node (ref "F1") (pin "2") (pinfunction "P$2_2") (pintype "passive"))
      (node (ref "R47") (pin "1") (pinfunction "1_1") (pintype "passive"))
      (node (ref "U16") (pin "P$1") (pinfunction "P$1_P$1") (pintype "passive"))
    )
    (net (code "89") (name "VSOLAR") (class "Default")
      (node (ref "C29") (pin "P$1") (pinfunction "1_P$1") (pintype "passive"))
      (node (ref "U16") (pin "P$5") (pinfunction "P$5_P$5") (pintype "power_in"))
    )
    (net (code "90") (name "unconnected-(U7-P$1-Pad1)") (class "Default")
      (node (ref "U7") (pin "1") (pinfunction "P$1_1") (pintype "output"))
    )
    (net (code "91") (name "unconnected-(U7-P$4-Pad4)") (class "Default")
      (node (ref "U7") (pin "4") (pinfunction "P$4_4") (pintype "passive"))
    )
    (net (code "92") (name "unconnected-(U9-PadP$4)") (class "Default")
      (node (ref "U9") (pin "P$4") (pinfunction "P$4_P$4") (pintype "output"))
    )
    (net (code "93") (name "unconnected-(U15-P$10-Pad10)") (class "Default")
      (node (ref "U15") (pin "10") (pinfunction "P$10_10") (pintype "passive"))
    )
    (net (code "94") (name "unconnected-(U16-PadP$4)") (class "Default")
      (node (ref "U16") (pin "P$4") (pinfunction "P$4_P$4") (pintype "output"))
    )
  )
)
